# led-er-v2_3b.net
KiCad netlist of a schematic drawn in EAGLE
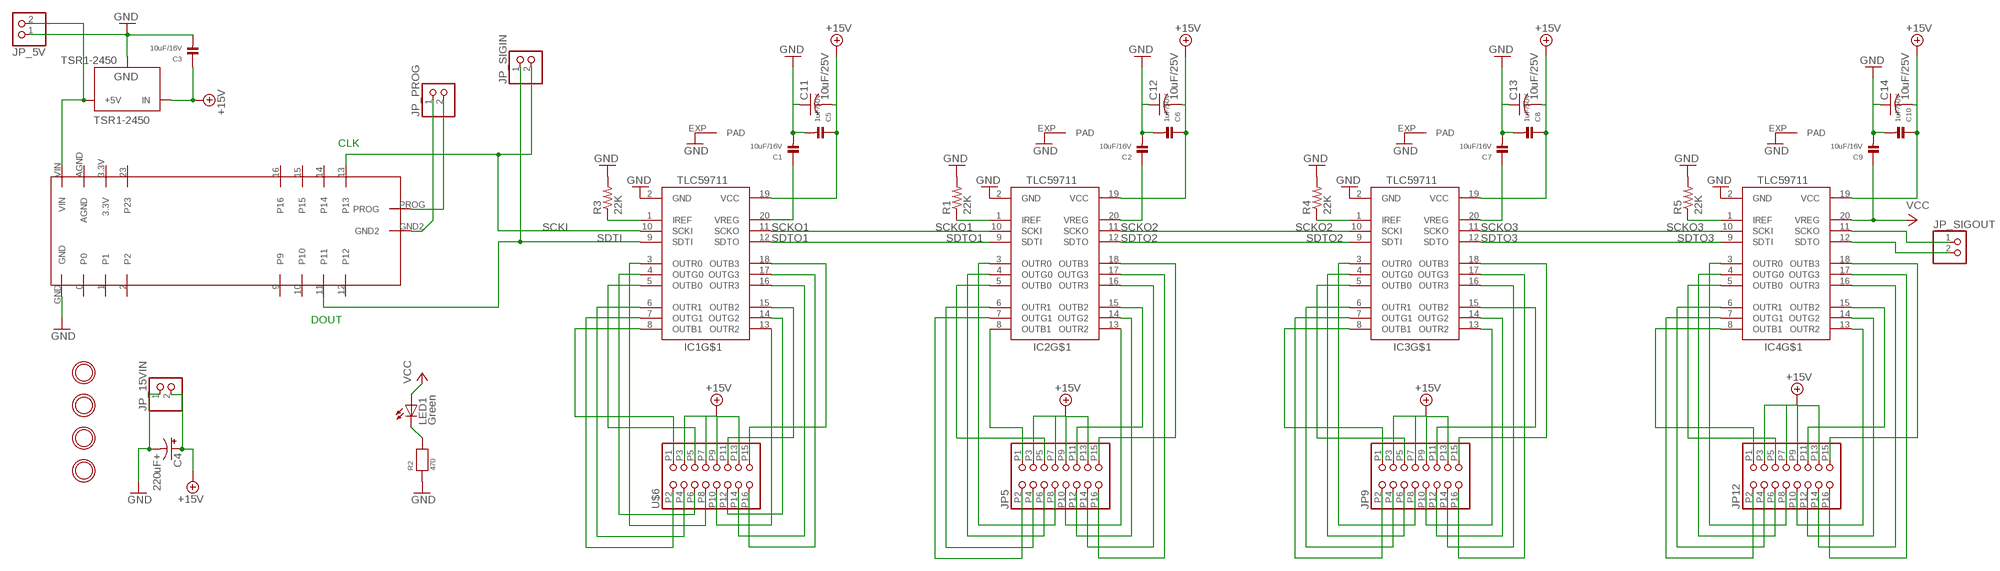
[diagram p0: schematic, sheet 1]

(export (version "E")
  (design (tool "Eeschema 10.0.6"))
  (components
    (comp (ref "C1")
      (value "10uF/16V")
      (footprint "eagle-import:0805")
      (libsource (lib "eagle-import") (part "CAP_CERAMIC0805"))
    )
    (comp (ref "C2")
      (value "10uF/16V")
      (footprint "eagle-import:0805")
      (libsource (lib "eagle-import") (part "CAP_CERAMIC0805"))
    )
    (comp (ref "C3")
      (value "10uF/16V")
      (footprint "eagle-import:0805")
      (libsource (lib "eagle-import") (part "CAP_CERAMIC0805"))
    )
    (comp (ref "C4")
      (value "220uF+")
      (footprint "eagle-import:E5-8,5")
      (libsource (lib "eagle-import") (part "CPOL-USE5-8.5"))
    )
    (comp (ref "C5")
      (value "1uF/50V")
      (footprint "eagle-import:0805")
      (libsource (lib "eagle-import") (part "CAP_CERAMIC0805"))
    )
    (comp (ref "C6")
      (value "1uF/50V")
      (footprint "eagle-import:0805")
      (libsource (lib "eagle-import") (part "CAP_CERAMIC0805"))
    )
    (comp (ref "C7")
      (value "10uF/16V")
      (footprint "eagle-import:0805")
      (libsource (lib "eagle-import") (part "CAP_CERAMIC0805"))
    )
    (comp (ref "C8")
      (value "1uF/50V")
      (footprint "eagle-import:0805")
      (libsource (lib "eagle-import") (part "CAP_CERAMIC0805"))
    )
    (comp (ref "C9")
      (value "10uF/16V")
      (footprint "eagle-import:0805")
      (libsource (lib "eagle-import") (part "CAP_CERAMIC0805"))
    )
    (comp (ref "C10")
      (value "1uF/50V")
      (footprint "eagle-import:0805")
      (libsource (lib "eagle-import") (part "CAP_CERAMIC0805"))
    )
    (comp (ref "C11")
      (value "10uF/25V")
      (footprint "eagle-import:C0805")
      (libsource (lib "eagle-import") (part "C-USC0805"))
    )
    (comp (ref "C12")
      (value "10uF/25V")
      (footprint "eagle-import:C0805")
      (libsource (lib "eagle-import") (part "C-USC0805"))
    )
    (comp (ref "C13")
      (value "10uF/25V")
      (footprint "eagle-import:C0805")
      (libsource (lib "eagle-import") (part "C-USC0805"))
    )
    (comp (ref "C14")
      (value "10uF/25V")
      (footprint "eagle-import:C0805")
      (libsource (lib "eagle-import") (part "C-USC0805"))
    )
    (comp (ref "IC1")
      (value "TLC59711")
      (footprint "eagle-import:HTSSOP20DAP")
      (libsource (lib "eagle-import") (part "TLC59711"))
    )
    (comp (ref "IC2")
      (value "TLC59711")
      (footprint "eagle-import:HTSSOP20DAP")
      (libsource (lib "eagle-import") (part "TLC59711"))
    )
    (comp (ref "IC3")
      (value "TLC59711")
      (footprint "eagle-import:HTSSOP20DAP")
      (libsource (lib "eagle-import") (part "TLC59711"))
    )
    (comp (ref "IC4")
      (value "TLC59711")
      (footprint "eagle-import:HTSSOP20DAP")
      (libsource (lib "eagle-import") (part "TLC59711"))
    )
    (comp (ref "JP5")
      (value "HEADER-2X8-RIBBON")
      (footprint "eagle-import:2X08_RIBBON")
      (libsource (lib "eagle-import") (part "HEADER-2X8-RIBBON"))
    )
    (comp (ref "JP9")
      (value "HEADER-2X8-RIBBON")
      (footprint "eagle-import:2X08_RIBBON")
      (libsource (lib "eagle-import") (part "HEADER-2X8-RIBBON"))
    )
    (comp (ref "JP12")
      (value "HEADER-2X8-RIBBON")
      (footprint "eagle-import:2X08_RIBBON")
      (libsource (lib "eagle-import") (part "HEADER-2X8-RIBBON"))
    )
    (comp (ref "JP_5V")
      (value "HEADER-1X2")
      (footprint "eagle-import:1X02_OVAL")
      (libsource (lib "eagle-import") (part "HEADER-1X2"))
    )
    (comp (ref "JP_15VIN")
      (value "HEADER-1X2")
      (footprint "eagle-import:1X02_OVAL")
      (libsource (lib "eagle-import") (part "HEADER-1X2"))
    )
    (comp (ref "JP_PROG")
      (value "HEADER-1X2")
      (footprint "eagle-import:1X02_OVAL")
      (libsource (lib "eagle-import") (part "HEADER-1X2"))
    )
    (comp (ref "JP_SIGIN")
      (value "HEADER-1X2")
      (footprint "eagle-import:1X02_OVAL")
      (libsource (lib "eagle-import") (part "HEADER-1X2"))
    )
    (comp (ref "JP_SIGOUT")
      (value "HEADER-1X2")
      (footprint "eagle-import:1X02_OVAL")
      (libsource (lib "eagle-import") (part "HEADER-1X2"))
    )
    (comp (ref "LED1")
      (value "Green")
      (footprint "eagle-import:CHIP-LED0805")
      (libsource (lib "eagle-import") (part "LEDCHIP-LED0805"))
    )
    (comp (ref "R1")
      (value "22K")
      (footprint "eagle-import:0805-THM-7")
      (libsource (lib "eagle-import") (part "R-US_FLIPFLOP7"))
    )
    (comp (ref "R2")
      (value "470")
      (footprint "eagle-import:0805")
      (libsource (lib "eagle-import") (part "RESISTOR0805"))
    )
    (comp (ref "R3")
      (value "22K")
      (footprint "eagle-import:0805-THM-7")
      (libsource (lib "eagle-import") (part "R-US_FLIPFLOP7"))
    )
    (comp (ref "R4")
      (value "22K")
      (footprint "eagle-import:0805-THM-7")
      (libsource (lib "eagle-import") (part "R-US_FLIPFLOP7"))
    )
    (comp (ref "R5")
      (value "22K")
      (footprint "eagle-import:0805-THM-7")
      (libsource (lib "eagle-import") (part "R-US_FLIPFLOP7"))
    )
    (comp (ref "TSR1-2450")
      (value "TSR1-2450")
      (footprint "eagle-import:TSR-1")
      (libsource (lib "eagle-import") (part "TSR1-2450"))
    )
    (comp (ref "U$1")
      (value "MOUNTINGHOLE")
      (footprint "eagle-import:MOUNTINGHOLE_3.0_PLATED")
      (libsource (lib "eagle-import") (part "MOUNTINGHOLE"))
    )
    (comp (ref "U$2")
      (value "MOUNTINGHOLE")
      (footprint "eagle-import:MOUNTINGHOLE_3.0_PLATED")
      (libsource (lib "eagle-import") (part "MOUNTINGHOLE"))
    )
    (comp (ref "U$3")
      (value "MOUNTINGHOLE")
      (footprint "eagle-import:MOUNTINGHOLE_3.0_PLATED")
      (libsource (lib "eagle-import") (part "MOUNTINGHOLE"))
    )
    (comp (ref "U$4")
      (value "MOUNTINGHOLE")
      (footprint "eagle-import:MOUNTINGHOLE_3.0_PLATED")
      (libsource (lib "eagle-import") (part "MOUNTINGHOLE"))
    )
    (comp (ref "U$5")
      (value "TEENSY_LEDER")
      (footprint "eagle-import:TEENSY_LEDER")
      (libsource (lib "eagle-import") (part "TEENSY_LEDER"))
    )
    (comp (ref "U$6")
      (value "HEADER-2X8-RIBBON")
      (footprint "eagle-import:2X08_RIBBON")
      (libsource (lib "eagle-import") (part "HEADER-2X8-RIBBON"))
    )
  )
  (nets
    (net (code "1") (name "+15V") (class "Default")
      (node (ref "C10") (pin "1") (pinfunction "P$1_1") (pintype "passive"))
      (node (ref "C11") (pin "2") (pinfunction "2_2") (pintype "passive"))
      (node (ref "C12") (pin "2") (pinfunction "2_2") (pintype "passive"))
      (node (ref "C13") (pin "2") (pinfunction "2_2") (pintype "passive"))
      (node (ref "C14") (pin "2") (pinfunction "2_2") (pintype "passive"))
      (node (ref "C3") (pin "1") (pinfunction "P$1_1") (pintype "passive"))
      (node (ref "C4") (pin "+") (pinfunction "+_+") (pintype "passive"))
      (node (ref "C5") (pin "1") (pinfunction "P$1_1") (pintype "passive"))
      (node (ref "C6") (pin "1") (pinfunction "P$1_1") (pintype "passive"))
      (node (ref "C8") (pin "1") (pinfunction "P$1_1") (pintype "passive"))
      (node (ref "IC1") (pin "19") (pinfunction "VCC_19") (pintype "power_in"))
      (node (ref "IC2") (pin "19") (pinfunction "VCC_19") (pintype "power_in"))
      (node (ref "IC3") (pin "19") (pinfunction "VCC_19") (pintype "power_in"))
      (node (ref "IC4") (pin "19") (pinfunction "VCC_19") (pintype "power_in"))
      (node (ref "JP12") (pin "P13") (pinfunction "P13_P13") (pintype "passive"))
      (node (ref "JP12") (pin "P3") (pinfunction "P3_P3") (pintype "passive"))
      (node (ref "JP12") (pin "P7") (pinfunction "P7_P7") (pintype "passive"))
      (node (ref "JP12") (pin "P9") (pinfunction "P9_P9") (pintype "passive"))
      (node (ref "JP5") (pin "P13") (pinfunction "P13_P13") (pintype "passive"))
      (node (ref "JP5") (pin "P3") (pinfunction "P3_P3") (pintype "passive"))
      (node (ref "JP5") (pin "P7") (pinfunction "P7_P7") (pintype "passive"))
      (node (ref "JP5") (pin "P9") (pinfunction "P9_P9") (pintype "passive"))
      (node (ref "JP9") (pin "P13") (pinfunction "P13_P13") (pintype "passive"))
      (node (ref "JP9") (pin "P3") (pinfunction "P3_P3") (pintype "passive"))
      (node (ref "JP9") (pin "P7") (pinfunction "P7_P7") (pintype "passive"))
      (node (ref "JP9") (pin "P9") (pinfunction "P9_P9") (pintype "passive"))
      (node (ref "JP_15VIN") (pin "2") (pinfunction "2_2") (pintype "passive"))
      (node (ref "TSR1-2450") (pin "1") (pinfunction "IN_1") (pintype "power_in"))
      (node (ref "U$6") (pin "P13") (pinfunction "P13_P13") (pintype "passive"))
      (node (ref "U$6") (pin "P3") (pinfunction "P3_P3") (pintype "passive"))
      (node (ref "U$6") (pin "P7") (pinfunction "P7_P7") (pintype "passive"))
      (node (ref "U$6") (pin "P9") (pinfunction "P9_P9") (pintype "passive"))
    )
    (net (code "2") (name "/SCKI") (class "Default")
      (node (ref "IC1") (pin "10") (pinfunction "SCKI_10") (pintype "input"))
      (node (ref "JP_SIGIN") (pin "2") (pinfunction "2_2") (pintype "passive"))
      (node (ref "U$5") (pin "13") (pinfunction "P13_13") (pintype "bidirectional"))
    )
    (net (code "3") (name "/SCKO1") (class "Default")
      (node (ref "IC1") (pin "11") (pinfunction "SCKO_11") (pintype "output"))
      (node (ref "IC2") (pin "10") (pinfunction "SCKI_10") (pintype "input"))
    )
    (net (code "4") (name "/SCKO2") (class "Default")
      (node (ref "IC2") (pin "11") (pinfunction "SCKO_11") (pintype "output"))
      (node (ref "IC3") (pin "10") (pinfunction "SCKI_10") (pintype "input"))
    )
    (net (code "5") (name "/SCKO3") (class "Default")
      (node (ref "IC3") (pin "11") (pinfunction "SCKO_11") (pintype "output"))
      (node (ref "IC4") (pin "10") (pinfunction "SCKI_10") (pintype "input"))
    )
    (net (code "6") (name "/SDTI") (class "Default")
      (node (ref "IC1") (pin "9") (pinfunction "SDTI_9") (pintype "input"))
      (node (ref "JP_SIGIN") (pin "1") (pinfunction "1_1") (pintype "passive"))
      (node (ref "U$5") (pin "11") (pinfunction "P11_11") (pintype "bidirectional"))
    )
    (net (code "7") (name "/SDTO1") (class "Default")
      (node (ref "IC1") (pin "12") (pinfunction "SDTO_12") (pintype "output"))
      (node (ref "IC2") (pin "9") (pinfunction "SDTI_9") (pintype "input"))
    )
    (net (code "8") (name "/SDTO2") (class "Default")
      (node (ref "IC2") (pin "12") (pinfunction "SDTO_12") (pintype "output"))
      (node (ref "IC3") (pin "9") (pinfunction "SDTI_9") (pintype "input"))
    )
    (net (code "9") (name "/SDTO3") (class "Default")
      (node (ref "IC3") (pin "12") (pinfunction "SDTO_12") (pintype "output"))
      (node (ref "IC4") (pin "9") (pinfunction "SDTI_9") (pintype "input"))
    )
    (net (code "10") (name "GND") (class "Default")
      (node (ref "C1") (pin "2") (pinfunction "P$2_2") (pintype "passive"))
      (node (ref "C10") (pin "2") (pinfunction "P$2_2") (pintype "passive"))
      (node (ref "C11") (pin "1") (pinfunction "1_1") (pintype "passive"))
      (node (ref "C12") (pin "1") (pinfunction "1_1") (pintype "passive"))
      (node (ref "C13") (pin "1") (pinfunction "1_1") (pintype "passive"))
      (node (ref "C14") (pin "1") (pinfunction "1_1") (pintype "passive"))
      (node (ref "C2") (pin "2") (pinfunction "P$2_2") (pintype "passive"))
      (node (ref "C3") (pin "2") (pinfunction "P$2_2") (pintype "passive"))
      (node (ref "C4") (pin "-") (pinfunction "-_-") (pintype "passive"))
      (node (ref "C5") (pin "2") (pinfunction "P$2_2") (pintype "passive"))
      (node (ref "C6") (pin "2") (pinfunction "P$2_2") (pintype "passive"))
      (node (ref "C7") (pin "2") (pinfunction "P$2_2") (pintype "passive"))
      (node (ref "C8") (pin "2") (pinfunction "P$2_2") (pintype "passive"))
      (node (ref "C9") (pin "2") (pinfunction "P$2_2") (pintype "passive"))
      (node (ref "IC1") (pin "2") (pinfunction "GND_2") (pintype "power_in"))
      (node (ref "IC1") (pin "EXP") (pinfunction "PAD_EXP") (pintype "passive"))
      (node (ref "IC2") (pin "2") (pinfunction "GND_2") (pintype "power_in"))
      (node (ref "IC2") (pin "EXP") (pinfunction "PAD_EXP") (pintype "passive"))
      (node (ref "IC3") (pin "2") (pinfunction "GND_2") (pintype "power_in"))
      (node (ref "IC3") (pin "EXP") (pinfunction "PAD_EXP") (pintype "passive"))
      (node (ref "IC4") (pin "2") (pinfunction "GND_2") (pintype "power_in"))
      (node (ref "IC4") (pin "EXP") (pinfunction "PAD_EXP") (pintype "passive"))
      (node (ref "JP_15VIN") (pin "1") (pinfunction "1_1") (pintype "passive"))
      (node (ref "JP_5V") (pin "1") (pinfunction "1_1") (pintype "passive"))
      (node (ref "R1") (pin "2") (pinfunction "2_2") (pintype "passive"))
      (node (ref "R2") (pin "1") (pinfunction "1_1") (pintype "passive"))
      (node (ref "R3") (pin "2") (pinfunction "2_2") (pintype "passive"))
      (node (ref "R4") (pin "2") (pinfunction "2_2") (pintype "passive"))
      (node (ref "R5") (pin "2") (pinfunction "2_2") (pintype "passive"))
      (node (ref "TSR1-2450") (pin "2") (pinfunction "GND_2") (pintype "power_in"))
      (node (ref "U$5") (pin "GND") (pinfunction "GND_GND") (pintype "bidirectional"))
    )
    (net (code "11") (name "Net-(C1-P$1)") (class "Default")
      (node (ref "C1") (pin "1") (pinfunction "P$1_1") (pintype "passive"))
      (node (ref "IC1") (pin "20") (pinfunction "VREG_20") (pintype "bidirectional"))
    )
    (net (code "12") (name "Net-(C2-P$1)") (class "Default")
      (node (ref "C2") (pin "1") (pinfunction "P$1_1") (pintype "passive"))
      (node (ref "IC2") (pin "20") (pinfunction "VREG_20") (pintype "bidirectional"))
    )
    (net (code "13") (name "Net-(C7-P$1)") (class "Default")
      (node (ref "C7") (pin "1") (pinfunction "P$1_1") (pintype "passive"))
      (node (ref "IC3") (pin "20") (pinfunction "VREG_20") (pintype "bidirectional"))
    )
    (net (code "14") (name "Net-(IC1A-IREF)") (class "Default")
      (node (ref "IC1") (pin "1") (pinfunction "IREF_1") (pintype "bidirectional"))
      (node (ref "R3") (pin "1") (pinfunction "1_1") (pintype "passive"))
    )
    (net (code "15") (name "Net-(IC1A-OUTB0)") (class "Default")
      (node (ref "IC1") (pin "5") (pinfunction "OUTB0_5") (pintype "open_collector"))
      (node (ref "U$6") (pin "P5") (pinfunction "P5_P5") (pintype "passive"))
    )
    (net (code "16") (name "Net-(IC1A-OUTB1)") (class "Default")
      (node (ref "IC1") (pin "8") (pinfunction "OUTB1_8") (pintype "open_collector"))
      (node (ref "U$6") (pin "P1") (pinfunction "P1_P1") (pintype "passive"))
    )
    (net (code "17") (name "Net-(IC1A-OUTB2)") (class "Default")
      (node (ref "IC1") (pin "15") (pinfunction "OUTB2_15") (pintype "open_collector"))
      (node (ref "U$6") (pin "P11") (pinfunction "P11_P11") (pintype "passive"))
    )
    (net (code "18") (name "Net-(IC1A-OUTB3)") (class "Default")
      (node (ref "IC1") (pin "18") (pinfunction "OUTB3_18") (pintype "open_collector"))
      (node (ref "U$6") (pin "P15") (pinfunction "P15_P15") (pintype "passive"))
    )
    (net (code "19") (name "Net-(IC1A-OUTG0)") (class "Default")
      (node (ref "IC1") (pin "4") (pinfunction "OUTG0_4") (pintype "open_collector"))
      (node (ref "U$6") (pin "P6") (pinfunction "P6_P6") (pintype "passive"))
    )
    (net (code "20") (name "Net-(IC1A-OUTG1)") (class "Default")
      (node (ref "IC1") (pin "7") (pinfunction "OUTG1_7") (pintype "open_collector"))
      (node (ref "U$6") (pin "P2") (pinfunction "P2_P2") (pintype "passive"))
    )
    (net (code "21") (name "Net-(IC1A-OUTG2)") (class "Default")
      (node (ref "IC1") (pin "14") (pinfunction "OUTG2_14") (pintype "open_collector"))
      (node (ref "U$6") (pin "P12") (pinfunction "P12_P12") (pintype "passive"))
    )
    (net (code "22") (name "Net-(IC1A-OUTG3)") (class "Default")
      (node (ref "IC1") (pin "17") (pinfunction "OUTG3_17") (pintype "open_collector"))
      (node (ref "U$6") (pin "P16") (pinfunction "P16_P16") (pintype "passive"))
    )
    (net (code "23") (name "Net-(IC1A-OUTR0)") (class "Default")
      (node (ref "IC1") (pin "3") (pinfunction "OUTR0_3") (pintype "open_collector"))
      (node (ref "U$6") (pin "P8") (pinfunction "P8_P8") (pintype "passive"))
    )
    (net (code "24") (name "Net-(IC1A-OUTR1)") (class "Default")
      (node (ref "IC1") (pin "6") (pinfunction "OUTR1_6") (pintype "open_collector"))
      (node (ref "U$6") (pin "P4") (pinfunction "P4_P4") (pintype "passive"))
    )
    (net (code "25") (name "Net-(IC1A-OUTR2)") (class "Default")
      (node (ref "IC1") (pin "13") (pinfunction "OUTR2_13") (pintype "open_collector"))
      (node (ref "U$6") (pin "P10") (pinfunction "P10_P10") (pintype "passive"))
    )
    (net (code "26") (name "Net-(IC1A-OUTR3)") (class "Default")
      (node (ref "IC1") (pin "16") (pinfunction "OUTR3_16") (pintype "open_collector"))
      (node (ref "U$6") (pin "P14") (pinfunction "P14_P14") (pintype "passive"))
    )
    (net (code "27") (name "Net-(IC2A-IREF)") (class "Default")
      (node (ref "IC2") (pin "1") (pinfunction "IREF_1") (pintype "bidirectional"))
      (node (ref "R1") (pin "1") (pinfunction "1_1") (pintype "passive"))
    )
    (net (code "28") (name "Net-(IC2A-OUTB0)") (class "Default")
      (node (ref "IC2") (pin "5") (pinfunction "OUTB0_5") (pintype "open_collector"))
      (node (ref "JP5") (pin "P5") (pinfunction "P5_P5") (pintype "passive"))
    )
    (net (code "29") (name "Net-(IC2A-OUTB1)") (class "Default")
      (node (ref "IC2") (pin "8") (pinfunction "OUTB1_8") (pintype "open_collector"))
      (node (ref "JP5") (pin "P1") (pinfunction "P1_P1") (pintype "passive"))
    )
    (net (code "30") (name "Net-(IC2A-OUTB2)") (class "Default")
      (node (ref "IC2") (pin "15") (pinfunction "OUTB2_15") (pintype "open_collector"))
      (node (ref "JP5") (pin "P11") (pinfunction "P11_P11") (pintype "passive"))
    )
    (net (code "31") (name "Net-(IC2A-OUTB3)") (class "Default")
      (node (ref "IC2") (pin "18") (pinfunction "OUTB3_18") (pintype "open_collector"))
      (node (ref "JP5") (pin "P15") (pinfunction "P15_P15") (pintype "passive"))
    )
    (net (code "32") (name "Net-(IC2A-OUTG0)") (class "Default")
      (node (ref "IC2") (pin "4") (pinfunction "OUTG0_4") (pintype "open_collector"))
      (node (ref "JP5") (pin "P6") (pinfunction "P6_P6") (pintype "passive"))
    )
    (net (code "33") (name "Net-(IC2A-OUTG1)") (class "Default")
      (node (ref "IC2") (pin "7") (pinfunction "OUTG1_7") (pintype "open_collector"))
      (node (ref "JP5") (pin "P2") (pinfunction "P2_P2") (pintype "passive"))
    )
    (net (code "34") (name "Net-(IC2A-OUTG2)") (class "Default")
      (node (ref "IC2") (pin "14") (pinfunction "OUTG2_14") (pintype "open_collector"))
      (node (ref "JP5") (pin "P12") (pinfunction "P12_P12") (pintype "passive"))
    )
    (net (code "35") (name "Net-(IC2A-OUTG3)") (class "Default")
      (node (ref "IC2") (pin "17") (pinfunction "OUTG3_17") (pintype "open_collector"))
      (node (ref "JP5") (pin "P16") (pinfunction "P16_P16") (pintype "passive"))
    )
    (net (code "36") (name "Net-(IC2A-OUTR0)") (class "Default")
      (node (ref "IC2") (pin "3") (pinfunction "OUTR0_3") (pintype "open_collector"))
      (node (ref "JP5") (pin "P8") (pinfunction "P8_P8") (pintype "passive"))
    )
    (net (code "37") (name "Net-(IC2A-OUTR1)") (class "Default")
      (node (ref "IC2") (pin "6") (pinfunction "OUTR1_6") (pintype "open_collector"))
      (node (ref "JP5") (pin "P4") (pinfunction "P4_P4") (pintype "passive"))
    )
    (net (code "38") (name "Net-(IC2A-OUTR2)") (class "Default")
      (node (ref "IC2") (pin "13") (pinfunction "OUTR2_13") (pintype "open_collector"))
      (node (ref "JP5") (pin "P10") (pinfunction "P10_P10") (pintype "passive"))
    )
    (net (code "39") (name "Net-(IC2A-OUTR3)") (class "Default")
      (node (ref "IC2") (pin "16") (pinfunction "OUTR3_16") (pintype "open_collector"))
      (node (ref "JP5") (pin "P14") (pinfunction "P14_P14") (pintype "passive"))
    )
    (net (code "40") (name "Net-(IC3A-IREF)") (class "Default")
      (node (ref "IC3") (pin "1") (pinfunction "IREF_1") (pintype "bidirectional"))
      (node (ref "R4") (pin "1") (pinfunction "1_1") (pintype "passive"))
    )
    (net (code "41") (name "Net-(IC3A-OUTB0)") (class "Default")
      (node (ref "IC3") (pin "5") (pinfunction "OUTB0_5") (pintype "open_collector"))
      (node (ref "JP9") (pin "P5") (pinfunction "P5_P5") (pintype "passive"))
    )
    (net (code "42") (name "Net-(IC3A-OUTB1)") (class "Default")
      (node (ref "IC3") (pin "8") (pinfunction "OUTB1_8") (pintype "open_collector"))
      (node (ref "JP9") (pin "P1") (pinfunction "P1_P1") (pintype "passive"))
    )
    (net (code "43") (name "Net-(IC3A-OUTB2)") (class "Default")
      (node (ref "IC3") (pin "15") (pinfunction "OUTB2_15") (pintype "open_collector"))
      (node (ref "JP9") (pin "P11") (pinfunction "P11_P11") (pintype "passive"))
    )
    (net (code "44") (name "Net-(IC3A-OUTB3)") (class "Default")
      (node (ref "IC3") (pin "18") (pinfunction "OUTB3_18") (pintype "open_collector"))
      (node (ref "JP9") (pin "P15") (pinfunction "P15_P15") (pintype "passive"))
    )
    (net (code "45") (name "Net-(IC3A-OUTG0)") (class "Default")
      (node (ref "IC3") (pin "4") (pinfunction "OUTG0_4") (pintype "open_collector"))
      (node (ref "JP9") (pin "P6") (pinfunction "P6_P6") (pintype "passive"))
    )
    (net (code "46") (name "Net-(IC3A-OUTG1)") (class "Default")
      (node (ref "IC3") (pin "7") (pinfunction "OUTG1_7") (pintype "open_collector"))
      (node (ref "JP9") (pin "P2") (pinfunction "P2_P2") (pintype "passive"))
    )
    (net (code "47") (name "Net-(IC3A-OUTG2)") (class "Default")
      (node (ref "IC3") (pin "14") (pinfunction "OUTG2_14") (pintype "open_collector"))
      (node (ref "JP9") (pin "P12") (pinfunction "P12_P12") (pintype "passive"))
    )
    (net (code "48") (name "Net-(IC3A-OUTG3)") (class "Default")
      (node (ref "IC3") (pin "17") (pinfunction "OUTG3_17") (pintype "open_collector"))
      (node (ref "JP9") (pin "P16") (pinfunction "P16_P16") (pintype "passive"))
    )
    (net (code "49") (name "Net-(IC3A-OUTR0)") (class "Default")
      (node (ref "IC3") (pin "3") (pinfunction "OUTR0_3") (pintype "open_collector"))
      (node (ref "JP9") (pin "P8") (pinfunction "P8_P8") (pintype "passive"))
    )
    (net (code "50") (name "Net-(IC3A-OUTR1)") (class "Default")
      (node (ref "IC3") (pin "6") (pinfunction "OUTR1_6") (pintype "open_collector"))
      (node (ref "JP9") (pin "P4") (pinfunction "P4_P4") (pintype "passive"))
    )
    (net (code "51") (name "Net-(IC3A-OUTR2)") (class "Default")
      (node (ref "IC3") (pin "13") (pinfunction "OUTR2_13") (pintype "open_collector"))
      (node (ref "JP9") (pin "P10") (pinfunction "P10_P10") (pintype "passive"))
    )
    (net (code "52") (name "Net-(IC3A-OUTR3)") (class "Default")
      (node (ref "IC3") (pin "16") (pinfunction "OUTR3_16") (pintype "open_collector"))
      (node (ref "JP9") (pin "P14") (pinfunction "P14_P14") (pintype "passive"))
    )
    (net (code "53") (name "Net-(IC4A-IREF)") (class "Default")
      (node (ref "IC4") (pin "1") (pinfunction "IREF_1") (pintype "bidirectional"))
      (node (ref "R5") (pin "1") (pinfunction "1_1") (pintype "passive"))
    )
    (net (code "54") (name "Net-(IC4A-OUTB0)") (class "Default")
      (node (ref "IC4") (pin "5") (pinfunction "OUTB0_5") (pintype "open_collector"))
      (node (ref "JP12") (pin "P5") (pinfunction "P5_P5") (pintype "passive"))
    )
    (net (code "55") (name "Net-(IC4A-OUTB1)") (class "Default")
      (node (ref "IC4") (pin "8") (pinfunction "OUTB1_8") (pintype "open_collector"))
      (node (ref "JP12") (pin "P1") (pinfunction "P1_P1") (pintype "passive"))
    )
    (net (code "56") (name "Net-(IC4A-OUTB2)") (class "Default")
      (node (ref "IC4") (pin "15") (pinfunction "OUTB2_15") (pintype "open_collector"))
      (node (ref "JP12") (pin "P11") (pinfunction "P11_P11") (pintype "passive"))
    )
    (net (code "57") (name "Net-(IC4A-OUTB3)") (class "Default")
      (node (ref "IC4") (pin "18") (pinfunction "OUTB3_18") (pintype "open_collector"))
      (node (ref "JP12") (pin "P15") (pinfunction "P15_P15") (pintype "passive"))
    )
    (net (code "58") (name "Net-(IC4A-OUTG0)") (class "Default")
      (node (ref "IC4") (pin "4") (pinfunction "OUTG0_4") (pintype "open_collector"))
      (node (ref "JP12") (pin "P6") (pinfunction "P6_P6") (pintype "passive"))
    )
    (net (code "59") (name "Net-(IC4A-OUTG1)") (class "Default")
      (node (ref "IC4") (pin "7") (pinfunction "OUTG1_7") (pintype "open_collector"))
      (node (ref "JP12") (pin "P2") (pinfunction "P2_P2") (pintype "passive"))
    )
    (net (code "60") (name "Net-(IC4A-OUTG2)") (class "Default")
      (node (ref "IC4") (pin "14") (pinfunction "OUTG2_14") (pintype "open_collector"))
      (node (ref "JP12") (pin "P12") (pinfunction "P12_P12") (pintype "passive"))
    )
    (net (code "61") (name "Net-(IC4A-OUTG3)") (class "Default")
      (node (ref "IC4") (pin "17") (pinfunction "OUTG3_17") (pintype "open_collector"))
      (node (ref "JP12") (pin "P16") (pinfunction "P16_P16") (pintype "passive"))
    )
    (net (code "62") (name "Net-(IC4A-OUTR0)") (class "Default")
      (node (ref "IC4") (pin "3") (pinfunction "OUTR0_3") (pintype "open_collector"))
      (node (ref "JP12") (pin "P8") (pinfunction "P8_P8") (pintype "passive"))
    )
    (net (code "63") (name "Net-(IC4A-OUTR1)") (class "Default")
      (node (ref "IC4") (pin "6") (pinfunction "OUTR1_6") (pintype "open_collector"))
      (node (ref "JP12") (pin "P4") (pinfunction "P4_P4") (pintype "passive"))
    )
    (net (code "64") (name "Net-(IC4A-OUTR2)") (class "Default")
      (node (ref "IC4") (pin "13") (pinfunction "OUTR2_13") (pintype "open_collector"))
      (node (ref "JP12") (pin "P10") (pinfunction "P10_P10") (pintype "passive"))
    )
    (net (code "65") (name "Net-(IC4A-OUTR3)") (class "Default")
      (node (ref "IC4") (pin "16") (pinfunction "OUTR3_16") (pintype "open_collector"))
      (node (ref "JP12") (pin "P14") (pinfunction "P14_P14") (pintype "passive"))
    )
    (net (code "66") (name "Net-(IC4A-SCKO)") (class "Default")
      (node (ref "IC4") (pin "11") (pinfunction "SCKO_11") (pintype "output"))
      (node (ref "JP_SIGOUT") (pin "1") (pinfunction "1_1") (pintype "passive"))
    )
    (net (code "67") (name "Net-(IC4A-SDTO)") (class "Default")
      (node (ref "IC4") (pin "12") (pinfunction "SDTO_12") (pintype "output"))
      (node (ref "JP_SIGOUT") (pin "2") (pinfunction "2_2") (pintype "passive"))
    )
    (net (code "68") (name "Net-(JP_PROG-Pad1)") (class "Default")
      (node (ref "JP_PROG") (pin "1") (pinfunction "1_1") (pintype "passive"))
      (node (ref "U$5") (pin "GND2") (pinfunction "GND2_GND2") (pintype "bidirectional"))
    )
    (net (code "69") (name "Net-(JP_PROG-Pad2)") (class "Default")
      (node (ref "JP_PROG") (pin "2") (pinfunction "2_2") (pintype "passive"))
      (node (ref "U$5") (pin "PROG") (pinfunction "PROG_PROG") (pintype "bidirectional"))
    )
    (net (code "70") (name "Net-(LED1-PadC)") (class "Default")
      (node (ref "LED1") (pin "C") (pinfunction "C_C") (pintype "passive"))
      (node (ref "R2") (pin "2") (pinfunction "2_2") (pintype "passive"))
    )
    (net (code "71") (name "Net-(TSR1-2450-+5V)") (class "Default")
      (node (ref "JP_5V") (pin "2") (pinfunction "2_2") (pintype "passive"))
      (node (ref "TSR1-2450") (pin "3") (pinfunction "+5V_3") (pintype "power_in"))
      (node (ref "U$5") (pin "VIN") (pinfunction "VIN_VIN") (pintype "bidirectional"))
    )
    (net (code "72") (name "VCC") (class "Default")
      (node (ref "C9") (pin "1") (pinfunction "P$1_1") (pintype "passive"))
      (node (ref "IC4") (pin "20") (pinfunction "VREG_20") (pintype "bidirectional"))
      (node (ref "LED1") (pin "A") (pinfunction "A_A") (pintype "passive"))
    )
    (net (code "73") (name "unconnected-(U$5-P0-Pad0)") (class "Default")
      (node (ref "U$5") (pin "0") (pinfunction "P0_0") (pintype "bidirectional"))
    )
    (net (code "74") (name "unconnected-(U$5-P1-Pad1)") (class "Default")
      (node (ref "U$5") (pin "1") (pinfunction "P1_1") (pintype "bidirectional"))
    )
    (net (code "75") (name "unconnected-(U$5-P2-Pad2)") (class "Default")
      (node (ref "U$5") (pin "2") (pinfunction "P2_2") (pintype "bidirectional"))
    )
    (net (code "76") (name "unconnected-(U$5-P9-Pad9)") (class "Default")
      (node (ref "U$5") (pin "9") (pinfunction "P9_9") (pintype "bidirectional"))
    )
    (net (code "77") (name "unconnected-(U$5-P10-Pad10)") (class "Default")
      (node (ref "U$5") (pin "10") (pinfunction "P10_10") (pintype "bidirectional"))
    )
    (net (code "78") (name "unconnected-(U$5-P12-Pad12)") (class "Default")
      (node (ref "U$5") (pin "12") (pinfunction "P12_12") (pintype "bidirectional"))
    )
    (net (code "79") (name "unconnected-(U$5-P14-Pad14)") (class "Default")
      (node (ref "U$5") (pin "14") (pinfunction "P14_14") (pintype "bidirectional"))
    )
    (net (code "80") (name "unconnected-(U$5-P15-Pad15)") (class "Default")
      (node (ref "U$5") (pin "15") (pinfunction "P15_15") (pintype "bidirectional"))
    )
    (net (code "81") (name "unconnected-(U$5-P16-Pad16)") (class "Default")
      (node (ref "U$5") (pin "16") (pinfunction "P16_16") (pintype "bidirectional"))
    )
    (net (code "82") (name "unconnected-(U$5-P23-Pad23)") (class "Default")
      (node (ref "U$5") (pin "23") (pinfunction "P23_23") (pintype "bidirectional"))
    )
    (net (code "83") (name "unconnected-(U$5-Pad3.3V)") (class "Default")
      (node (ref "U$5") (pin "3.3V") (pinfunction "3.3V_3.3V") (pintype "bidirectional"))
    )
    (net (code "84") (name "unconnected-(U$5-PadAGND)") (class "Default")
      (node (ref "U$5") (pin "AGND") (pinfunction "AGND_AGND") (pintype "bidirectional"))
    )
  )
)
